# Four_Track_R0.net
KiCad netlist of a schematic drawn in EAGLE
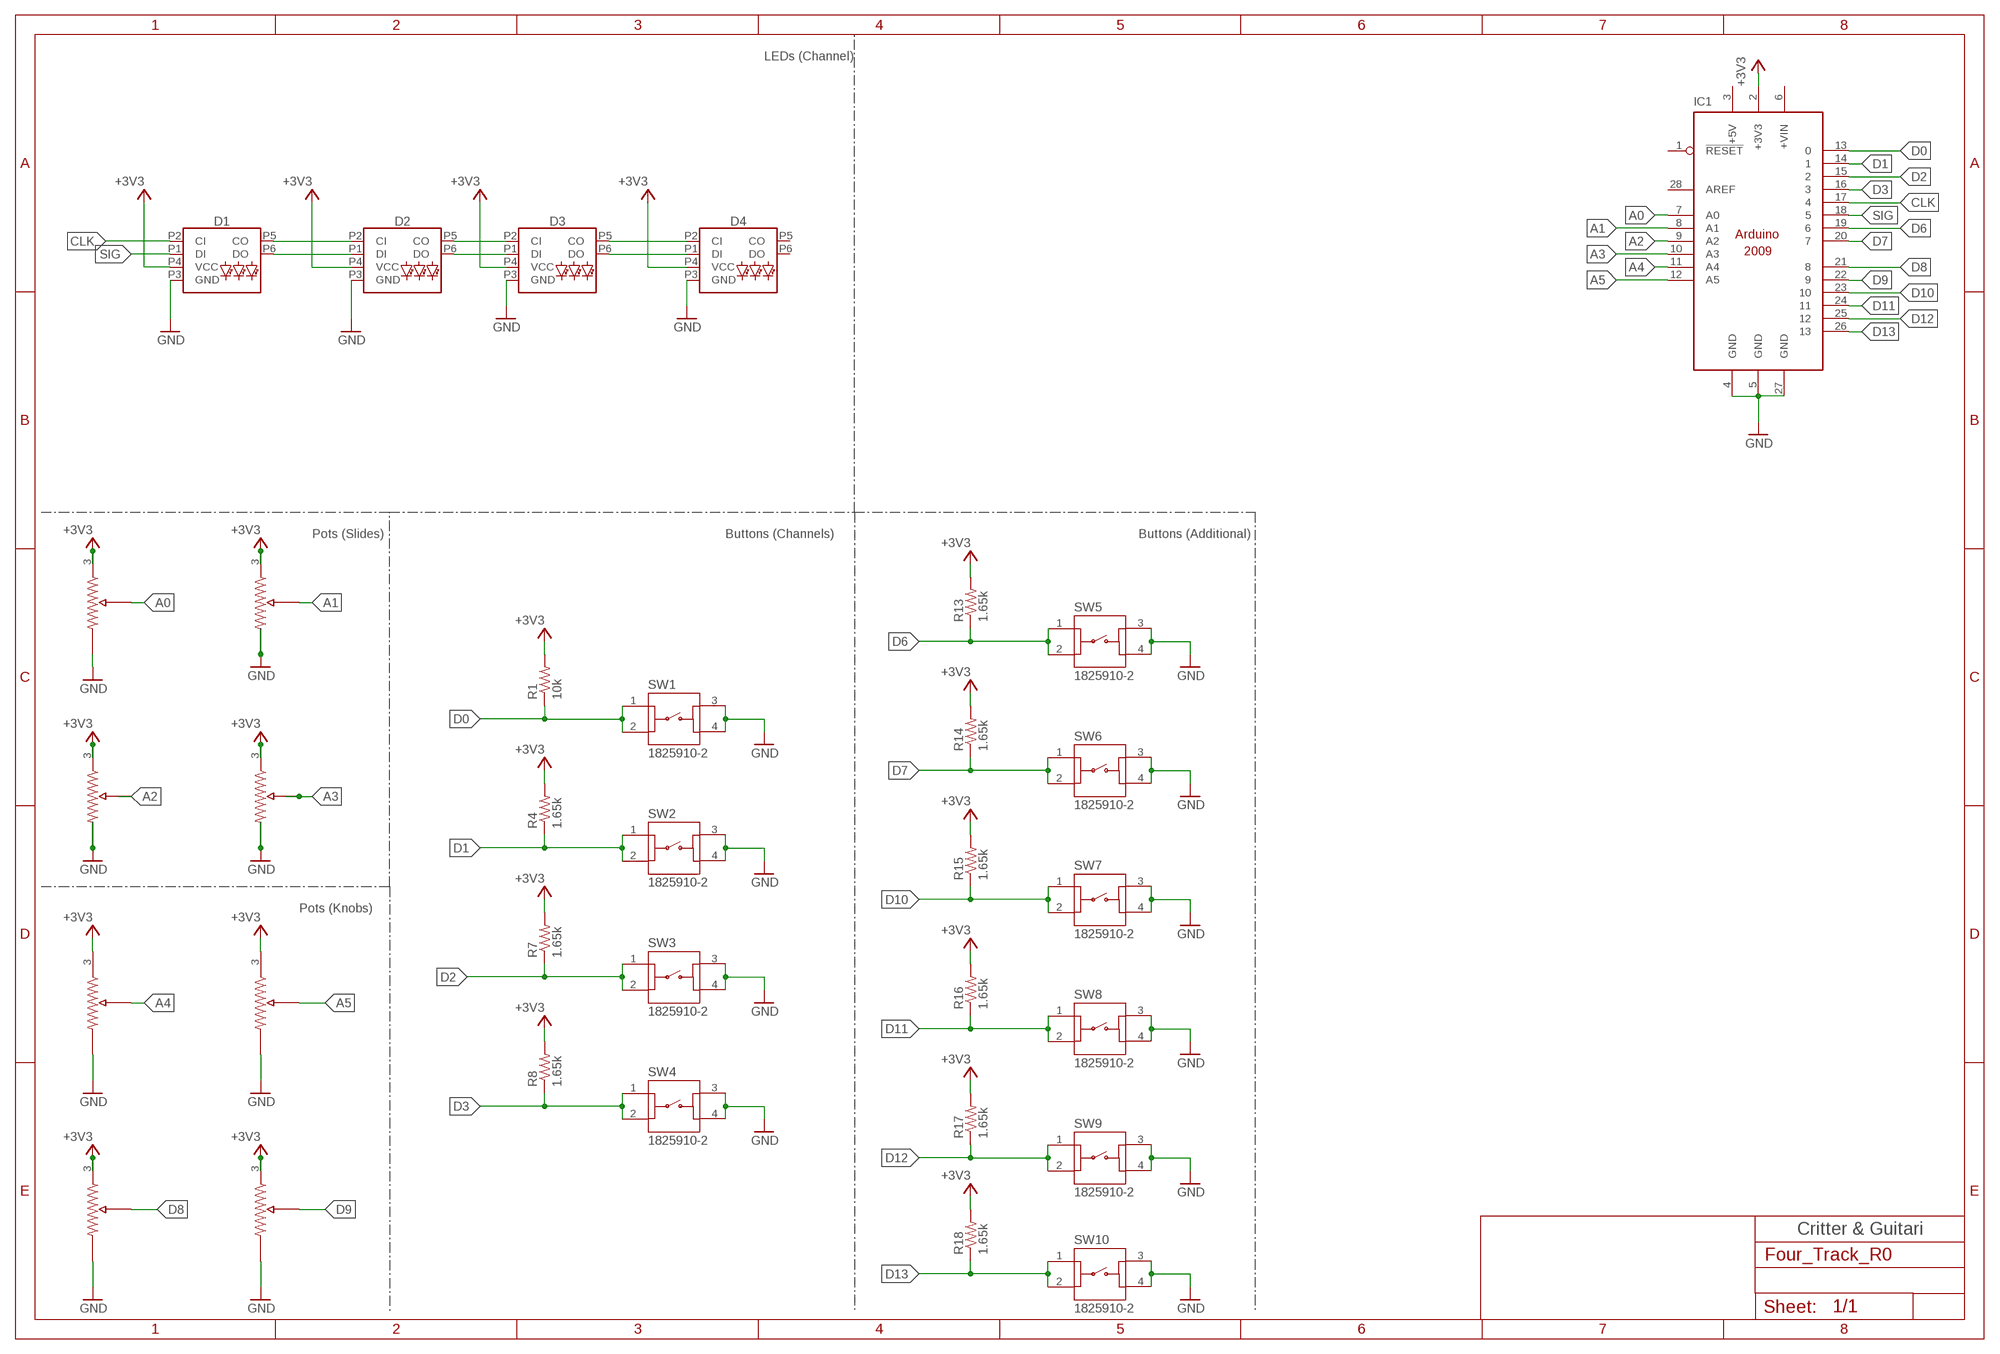
[diagram p0: schematic, sheet 1]

(export (version "E")
  (design (tool "Eeschema 10.0.6"))
  (components
    (comp (ref "D1")
      (value "SPARKFUN-LED_APA102-5050")
      (footprint "eagle-import:SPARKFUN-LED_APA102-5050")
      (libsource (lib "eagle-import") (part "SPARKFUN-LED_APA102-5050"))
    )
    (comp (ref "D2")
      (value "SPARKFUN-LED_APA102-5050")
      (footprint "eagle-import:SPARKFUN-LED_APA102-5050")
      (libsource (lib "eagle-import") (part "SPARKFUN-LED_APA102-5050"))
    )
    (comp (ref "D3")
      (value "SPARKFUN-LED_APA102-5050")
      (footprint "eagle-import:SPARKFUN-LED_APA102-5050")
      (libsource (lib "eagle-import") (part "SPARKFUN-LED_APA102-5050"))
    )
    (comp (ref "D4")
      (value "SPARKFUN-LED_APA102-5050")
      (footprint "eagle-import:SPARKFUN-LED_APA102-5050")
      (libsource (lib "eagle-import") (part "SPARKFUN-LED_APA102-5050"))
    )
    (comp (ref "IC1")
      (value "ARDUINO2009_10")
      (footprint "eagle-import:ARDUINO2009")
      (libsource (lib "eagle-import") (part "ARDUINO2009_10"))
    )
    (comp (ref "R1")
      (value "10k")
      (footprint "eagle-import:R0603")
      (libsource (lib "eagle-import") (part "R-US_R0603"))
    )
    (comp (ref "R2")
      (value "POTPTA45")
      (footprint "eagle-import:SLIDE_POT_PTA4543")
      (libsource (lib "eagle-import") (part "POTPTA45"))
    )
    (comp (ref "R3")
      (value "POTPTA45")
      (footprint "eagle-import:SLIDE_POT_PTA4543")
      (libsource (lib "eagle-import") (part "POTPTA45"))
    )
    (comp (ref "R4")
      (value "1.65k")
      (footprint "eagle-import:R0603")
      (libsource (lib "eagle-import") (part "R-US_R0603"))
    )
    (comp (ref "R5")
      (value "POTPTA45")
      (footprint "eagle-import:SLIDE_POT_PTA4543")
      (libsource (lib "eagle-import") (part "POTPTA45"))
    )
    (comp (ref "R6")
      (value "POTVERT")
      (footprint "eagle-import:POT-P09X-VERT")
      (libsource (lib "eagle-import") (part "POTVERT"))
    )
    (comp (ref "R7")
      (value "1.65k")
      (footprint "eagle-import:R0603")
      (libsource (lib "eagle-import") (part "R-US_R0603"))
    )
    (comp (ref "R8")
      (value "1.65k")
      (footprint "eagle-import:R0603")
      (libsource (lib "eagle-import") (part "R-US_R0603"))
    )
    (comp (ref "R9")
      (value "POTVERT")
      (footprint "eagle-import:POT-P09X-VERT")
      (libsource (lib "eagle-import") (part "POTVERT"))
    )
    (comp (ref "R10")
      (value "POTVERT")
      (footprint "eagle-import:POT-P09X-VERT")
      (libsource (lib "eagle-import") (part "POTVERT"))
    )
    (comp (ref "R11")
      (value "POTPTA45")
      (footprint "eagle-import:SLIDE_POT_PTA4543")
      (libsource (lib "eagle-import") (part "POTPTA45"))
    )
    (comp (ref "R12")
      (value "POTVERT")
      (footprint "eagle-import:POT-P09X-VERT")
      (libsource (lib "eagle-import") (part "POTVERT"))
    )
    (comp (ref "R13")
      (value "1.65k")
      (footprint "eagle-import:R0603")
      (libsource (lib "eagle-import") (part "R-US_R0603"))
    )
    (comp (ref "R14")
      (value "1.65k")
      (footprint "eagle-import:R0603")
      (libsource (lib "eagle-import") (part "R-US_R0603"))
    )
    (comp (ref "R15")
      (value "1.65k")
      (footprint "eagle-import:R0603")
      (libsource (lib "eagle-import") (part "R-US_R0603"))
    )
    (comp (ref "R16")
      (value "1.65k")
      (footprint "eagle-import:R0603")
      (libsource (lib "eagle-import") (part "R-US_R0603"))
    )
    (comp (ref "R17")
      (value "1.65k")
      (footprint "eagle-import:R0603")
      (libsource (lib "eagle-import") (part "R-US_R0603"))
    )
    (comp (ref "R18")
      (value "1.65k")
      (footprint "eagle-import:R0603")
      (libsource (lib "eagle-import") (part "R-US_R0603"))
    )
    (comp (ref "SW1")
      (value "1825910-2")
      (footprint "eagle-import:TE_1825910-2")
      (fields (field (name "MF") "TE Connectivity"))
      (libsource (lib "eagle-import") (part "1825910-2"))
    )
    (comp (ref "SW2")
      (value "1825910-2")
      (footprint "eagle-import:TE_1825910-2")
      (fields (field (name "MF") "TE Connectivity"))
      (libsource (lib "eagle-import") (part "1825910-2"))
    )
    (comp (ref "SW3")
      (value "1825910-2")
      (footprint "eagle-import:TE_1825910-2")
      (fields (field (name "MF") "TE Connectivity"))
      (libsource (lib "eagle-import") (part "1825910-2"))
    )
    (comp (ref "SW4")
      (value "1825910-2")
      (footprint "eagle-import:TE_1825910-2")
      (fields (field (name "MF") "TE Connectivity"))
      (libsource (lib "eagle-import") (part "1825910-2"))
    )
    (comp (ref "SW5")
      (value "1825910-2")
      (footprint "eagle-import:TE_1825910-2")
      (fields (field (name "MF") "TE Connectivity"))
      (libsource (lib "eagle-import") (part "1825910-2"))
    )
    (comp (ref "SW6")
      (value "1825910-2")
      (footprint "eagle-import:TE_1825910-2")
      (fields (field (name "MF") "TE Connectivity"))
      (libsource (lib "eagle-import") (part "1825910-2"))
    )
    (comp (ref "SW7")
      (value "1825910-2")
      (footprint "eagle-import:TE_1825910-2")
      (fields (field (name "MF") "TE Connectivity"))
      (libsource (lib "eagle-import") (part "1825910-2"))
    )
    (comp (ref "SW8")
      (value "1825910-2")
      (footprint "eagle-import:TE_1825910-2")
      (fields (field (name "MF") "TE Connectivity"))
      (libsource (lib "eagle-import") (part "1825910-2"))
    )
    (comp (ref "SW9")
      (value "1825910-2")
      (footprint "eagle-import:TE_1825910-2")
      (fields (field (name "MF") "TE Connectivity"))
      (libsource (lib "eagle-import") (part "1825910-2"))
    )
    (comp (ref "SW10")
      (value "1825910-2")
      (footprint "eagle-import:TE_1825910-2")
      (fields (field (name "MF") "TE Connectivity"))
      (libsource (lib "eagle-import") (part "1825910-2"))
    )
  )
  (nets
    (net (code "1") (name "+3V3") (class "Default")
      (node (ref "D1") (pin "P4") (pinfunction "VCC_P4") (pintype "bidirectional"))
      (node (ref "D2") (pin "P4") (pinfunction "VCC_P4") (pintype "bidirectional"))
      (node (ref "D3") (pin "P4") (pinfunction "VCC_P4") (pintype "bidirectional"))
      (node (ref "D4") (pin "P4") (pinfunction "VCC_P4") (pintype "bidirectional"))
      (node (ref "IC1") (pin "2") (pinfunction "+3V3_2") (pintype "power_in"))
      (node (ref "R1") (pin "2") (pinfunction "2_2") (pintype "passive"))
      (node (ref "R10") (pin "3") (pinfunction "P$3_3") (pintype "bidirectional"))
      (node (ref "R11") (pin "3") (pinfunction "P$3_3") (pintype "bidirectional"))
      (node (ref "R12") (pin "3") (pinfunction "P$3_3") (pintype "bidirectional"))
      (node (ref "R13") (pin "2") (pinfunction "2_2") (pintype "passive"))
      (node (ref "R14") (pin "2") (pinfunction "2_2") (pintype "passive"))
      (node (ref "R15") (pin "2") (pinfunction "2_2") (pintype "passive"))
      (node (ref "R16") (pin "2") (pinfunction "2_2") (pintype "passive"))
      (node (ref "R17") (pin "2") (pinfunction "2_2") (pintype "passive"))
      (node (ref "R18") (pin "2") (pinfunction "2_2") (pintype "passive"))
      (node (ref "R2") (pin "3") (pinfunction "P$3_3") (pintype "bidirectional"))
      (node (ref "R3") (pin "3") (pinfunction "P$3_3") (pintype "bidirectional"))
      (node (ref "R4") (pin "2") (pinfunction "2_2") (pintype "passive"))
      (node (ref "R5") (pin "3") (pinfunction "P$3_3") (pintype "bidirectional"))
      (node (ref "R6") (pin "3") (pinfunction "P$3_3") (pintype "bidirectional"))
      (node (ref "R7") (pin "2") (pinfunction "2_2") (pintype "passive"))
      (node (ref "R8") (pin "2") (pinfunction "2_2") (pintype "passive"))
      (node (ref "R9") (pin "3") (pinfunction "P$3_3") (pintype "bidirectional"))
    )
    (net (code "2") (name "/+5V") (class "Default")
      (node (ref "IC1") (pin "3") (pinfunction "+5V_3") (pintype "power_in"))
    )
    (net (code "3") (name "A0") (class "Default")
      (node (ref "IC1") (pin "7") (pinfunction "A0_7") (pintype "bidirectional"))
      (node (ref "R11") (pin "2") (pinfunction "P$1_2") (pintype "bidirectional"))
    )
    (net (code "4") (name "A1") (class "Default")
      (node (ref "IC1") (pin "8") (pinfunction "A1_8") (pintype "bidirectional"))
      (node (ref "R5") (pin "2") (pinfunction "P$1_2") (pintype "bidirectional"))
    )
    (net (code "5") (name "A2") (class "Default")
      (node (ref "IC1") (pin "9") (pinfunction "A2_9") (pintype "bidirectional"))
      (node (ref "R2") (pin "2") (pinfunction "P$1_2") (pintype "bidirectional"))
    )
    (net (code "6") (name "A3") (class "Default")
      (node (ref "IC1") (pin "10") (pinfunction "A3_10") (pintype "bidirectional"))
      (node (ref "R3") (pin "2") (pinfunction "P$1_2") (pintype "bidirectional"))
    )
    (net (code "7") (name "A4") (class "Default")
      (node (ref "IC1") (pin "11") (pinfunction "A4_11") (pintype "bidirectional"))
      (node (ref "R9") (pin "WIPER") (pinfunction "P$1_WIPER") (pintype "bidirectional"))
    )
    (net (code "8") (name "A5") (class "Default")
      (node (ref "IC1") (pin "12") (pinfunction "A5_12") (pintype "bidirectional"))
      (node (ref "R10") (pin "WIPER") (pinfunction "P$1_WIPER") (pintype "bidirectional"))
    )
    (net (code "9") (name "CLK") (class "Default")
      (node (ref "D1") (pin "P2") (pinfunction "CI_P2") (pintype "bidirectional"))
      (node (ref "IC1") (pin "17") (pinfunction "4_17") (pintype "bidirectional"))
    )
    (net (code "10") (name "D0") (class "Default")
      (node (ref "IC1") (pin "13") (pinfunction "0_13") (pintype "bidirectional"))
      (node (ref "R1") (pin "1") (pinfunction "1_1") (pintype "passive"))
      (node (ref "SW1") (pin "1") (pinfunction "1_1") (pintype "passive"))
      (node (ref "SW1") (pin "2") (pinfunction "2_2") (pintype "passive"))
    )
    (net (code "11") (name "D1") (class "Default")
      (node (ref "IC1") (pin "14") (pinfunction "1_14") (pintype "bidirectional"))
      (node (ref "R4") (pin "1") (pinfunction "1_1") (pintype "passive"))
      (node (ref "SW2") (pin "1") (pinfunction "1_1") (pintype "passive"))
      (node (ref "SW2") (pin "2") (pinfunction "2_2") (pintype "passive"))
    )
    (net (code "12") (name "D2") (class "Default")
      (node (ref "IC1") (pin "15") (pinfunction "2_15") (pintype "bidirectional"))
      (node (ref "R7") (pin "1") (pinfunction "1_1") (pintype "passive"))
      (node (ref "SW3") (pin "1") (pinfunction "1_1") (pintype "passive"))
      (node (ref "SW3") (pin "2") (pinfunction "2_2") (pintype "passive"))
    )
    (net (code "13") (name "D3") (class "Default")
      (node (ref "IC1") (pin "16") (pinfunction "3_16") (pintype "bidirectional"))
      (node (ref "R8") (pin "1") (pinfunction "1_1") (pintype "passive"))
      (node (ref "SW4") (pin "1") (pinfunction "1_1") (pintype "passive"))
      (node (ref "SW4") (pin "2") (pinfunction "2_2") (pintype "passive"))
    )
    (net (code "14") (name "D6") (class "Default")
      (node (ref "IC1") (pin "19") (pinfunction "6_19") (pintype "bidirectional"))
      (node (ref "R13") (pin "1") (pinfunction "1_1") (pintype "passive"))
      (node (ref "SW5") (pin "1") (pinfunction "1_1") (pintype "passive"))
      (node (ref "SW5") (pin "2") (pinfunction "2_2") (pintype "passive"))
    )
    (net (code "15") (name "D7") (class "Default")
      (node (ref "IC1") (pin "20") (pinfunction "7_20") (pintype "bidirectional"))
      (node (ref "R14") (pin "1") (pinfunction "1_1") (pintype "passive"))
      (node (ref "SW6") (pin "1") (pinfunction "1_1") (pintype "passive"))
      (node (ref "SW6") (pin "2") (pinfunction "2_2") (pintype "passive"))
    )
    (net (code "16") (name "D8") (class "Default")
      (node (ref "IC1") (pin "21") (pinfunction "8_21") (pintype "bidirectional"))
      (node (ref "R6") (pin "WIPER") (pinfunction "P$1_WIPER") (pintype "bidirectional"))
    )
    (net (code "17") (name "D9") (class "Default")
      (node (ref "IC1") (pin "22") (pinfunction "9_22") (pintype "bidirectional"))
      (node (ref "R12") (pin "WIPER") (pinfunction "P$1_WIPER") (pintype "bidirectional"))
    )
    (net (code "18") (name "D10") (class "Default")
      (node (ref "IC1") (pin "23") (pinfunction "10_23") (pintype "bidirectional"))
      (node (ref "R15") (pin "1") (pinfunction "1_1") (pintype "passive"))
      (node (ref "SW7") (pin "1") (pinfunction "1_1") (pintype "passive"))
      (node (ref "SW7") (pin "2") (pinfunction "2_2") (pintype "passive"))
    )
    (net (code "19") (name "D11") (class "Default")
      (node (ref "IC1") (pin "24") (pinfunction "11_24") (pintype "bidirectional"))
      (node (ref "R16") (pin "1") (pinfunction "1_1") (pintype "passive"))
      (node (ref "SW8") (pin "1") (pinfunction "1_1") (pintype "passive"))
      (node (ref "SW8") (pin "2") (pinfunction "2_2") (pintype "passive"))
    )
    (net (code "20") (name "D12") (class "Default")
      (node (ref "IC1") (pin "25") (pinfunction "12_25") (pintype "bidirectional"))
      (node (ref "R17") (pin "1") (pinfunction "1_1") (pintype "passive"))
      (node (ref "SW9") (pin "1") (pinfunction "1_1") (pintype "passive"))
      (node (ref "SW9") (pin "2") (pinfunction "2_2") (pintype "passive"))
    )
    (net (code "21") (name "D13") (class "Default")
      (node (ref "IC1") (pin "26") (pinfunction "13_26") (pintype "bidirectional"))
      (node (ref "R18") (pin "1") (pinfunction "1_1") (pintype "passive"))
      (node (ref "SW10") (pin "1") (pinfunction "1_1") (pintype "passive"))
      (node (ref "SW10") (pin "2") (pinfunction "2_2") (pintype "passive"))
    )
    (net (code "22") (name "GND") (class "Default")
      (node (ref "D1") (pin "P3") (pinfunction "GND_P3") (pintype "bidirectional"))
      (node (ref "D2") (pin "P3") (pinfunction "GND_P3") (pintype "bidirectional"))
      (node (ref "D3") (pin "P3") (pinfunction "GND_P3") (pintype "bidirectional"))
      (node (ref "D4") (pin "P3") (pinfunction "GND_P3") (pintype "bidirectional"))
      (node (ref "IC1") (pin "27") (pinfunction "GND_27") (pintype "power_in"))
      (node (ref "IC1") (pin "4") (pinfunction "GND_4") (pintype "power_in"))
      (node (ref "IC1") (pin "5") (pinfunction "GND_5") (pintype "power_in"))
      (node (ref "R10") (pin "1") (pinfunction "P$2_1") (pintype "bidirectional"))
      (node (ref "R11") (pin "1") (pinfunction "P$2_1") (pintype "bidirectional"))
      (node (ref "R12") (pin "1") (pinfunction "P$2_1") (pintype "bidirectional"))
      (node (ref "R2") (pin "1") (pinfunction "P$2_1") (pintype "bidirectional"))
      (node (ref "R3") (pin "1") (pinfunction "P$2_1") (pintype "bidirectional"))
      (node (ref "R5") (pin "1") (pinfunction "P$2_1") (pintype "bidirectional"))
      (node (ref "R6") (pin "1") (pinfunction "P$2_1") (pintype "bidirectional"))
      (node (ref "R9") (pin "1") (pinfunction "P$2_1") (pintype "bidirectional"))
      (node (ref "SW1") (pin "3") (pinfunction "3_3") (pintype "passive"))
      (node (ref "SW1") (pin "4") (pinfunction "4_4") (pintype "passive"))
      (node (ref "SW10") (pin "3") (pinfunction "3_3") (pintype "passive"))
      (node (ref "SW10") (pin "4") (pinfunction "4_4") (pintype "passive"))
      (node (ref "SW2") (pin "3") (pinfunction "3_3") (pintype "passive"))
      (node (ref "SW2") (pin "4") (pinfunction "4_4") (pintype "passive"))
      (node (ref "SW3") (pin "3") (pinfunction "3_3") (pintype "passive"))
      (node (ref "SW3") (pin "4") (pinfunction "4_4") (pintype "passive"))
      (node (ref "SW4") (pin "3") (pinfunction "3_3") (pintype "passive"))
      (node (ref "SW4") (pin "4") (pinfunction "4_4") (pintype "passive"))
      (node (ref "SW5") (pin "3") (pinfunction "3_3") (pintype "passive"))
      (node (ref "SW5") (pin "4") (pinfunction "4_4") (pintype "passive"))
      (node (ref "SW6") (pin "3") (pinfunction "3_3") (pintype "passive"))
      (node (ref "SW6") (pin "4") (pinfunction "4_4") (pintype "passive"))
      (node (ref "SW7") (pin "3") (pinfunction "3_3") (pintype "passive"))
      (node (ref "SW7") (pin "4") (pinfunction "4_4") (pintype "passive"))
      (node (ref "SW8") (pin "3") (pinfunction "3_3") (pintype "passive"))
      (node (ref "SW8") (pin "4") (pinfunction "4_4") (pintype "passive"))
      (node (ref "SW9") (pin "3") (pinfunction "3_3") (pintype "passive"))
      (node (ref "SW9") (pin "4") (pinfunction "4_4") (pintype "passive"))
    )
    (net (code "23") (name "Net-(D1-CO)") (class "Default")
      (node (ref "D1") (pin "P5") (pinfunction "CO_P5") (pintype "bidirectional"))
      (node (ref "D2") (pin "P2") (pinfunction "CI_P2") (pintype "bidirectional"))
    )
    (net (code "24") (name "Net-(D1-DO)") (class "Default")
      (node (ref "D1") (pin "P6") (pinfunction "DO_P6") (pintype "bidirectional"))
      (node (ref "D2") (pin "P1") (pinfunction "DI_P1") (pintype "bidirectional"))
    )
    (net (code "25") (name "Net-(D2-CO)") (class "Default")
      (node (ref "D2") (pin "P5") (pinfunction "CO_P5") (pintype "bidirectional"))
      (node (ref "D3") (pin "P2") (pinfunction "CI_P2") (pintype "bidirectional"))
    )
    (net (code "26") (name "Net-(D2-DO)") (class "Default")
      (node (ref "D2") (pin "P6") (pinfunction "DO_P6") (pintype "bidirectional"))
      (node (ref "D3") (pin "P1") (pinfunction "DI_P1") (pintype "bidirectional"))
    )
    (net (code "27") (name "Net-(D3-CO)") (class "Default")
      (node (ref "D3") (pin "P5") (pinfunction "CO_P5") (pintype "bidirectional"))
      (node (ref "D4") (pin "P2") (pinfunction "CI_P2") (pintype "bidirectional"))
    )
    (net (code "28") (name "Net-(D3-DO)") (class "Default")
      (node (ref "D3") (pin "P6") (pinfunction "DO_P6") (pintype "bidirectional"))
      (node (ref "D4") (pin "P1") (pinfunction "DI_P1") (pintype "bidirectional"))
    )
    (net (code "29") (name "SIG") (class "Default")
      (node (ref "D1") (pin "P1") (pinfunction "DI_P1") (pintype "bidirectional"))
      (node (ref "IC1") (pin "18") (pinfunction "5_18") (pintype "bidirectional"))
    )
    (net (code "30") (name "unconnected-(D4-CO-PadP5)") (class "Default")
      (node (ref "D4") (pin "P5") (pinfunction "CO_P5") (pintype "bidirectional"))
    )
    (net (code "31") (name "unconnected-(D4-DO-PadP6)") (class "Default")
      (node (ref "D4") (pin "P6") (pinfunction "DO_P6") (pintype "bidirectional"))
    )
    (net (code "32") (name "unconnected-(IC1-+VIN-Pad6)") (class "Default")
      (node (ref "IC1") (pin "6") (pinfunction "+VIN_6") (pintype "bidirectional"))
    )
    (net (code "33") (name "unconnected-(IC1-AREF-Pad28)") (class "Default")
      (node (ref "IC1") (pin "28") (pinfunction "AREF_28") (pintype "bidirectional"))
    )
    (net (code "34") (name "unconnected-(IC1-~{RESET}-Pad1)") (class "Default")
      (node (ref "IC1") (pin "1") (pinfunction "~{RESET}_1") (pintype "bidirectional"))
    )
  )
)
